# R_Phase_Sense_Signal_Isolation.net
KiCad netlist of a schematic drawn in Altium Designer
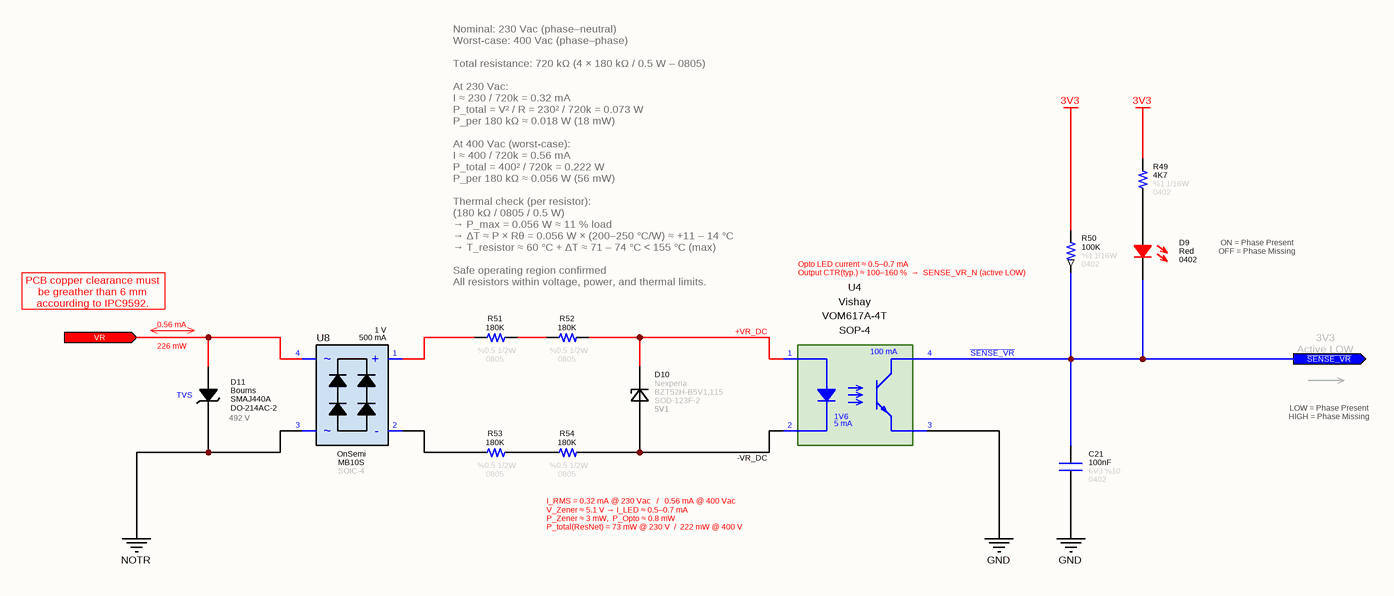
[diagram p0: R Phase Sense Signal Isolation.SchDoc]

(export (version "E")
  (design (tool "Eeschema 10.0.6"))
  (components
    (comp (ref "C21")
      (value "100nF")
      (footprint "CAPACITOR_0402")
      (description "Capacitor (MLCC) - 100nF / 6V3 / 0402")
      (fields
        (field (name "MANUFACTURER PART NUMBER") "04026D104KAT4A")
        (field (name "TOLERANCE") "%10")
        (field (name "VOLTAGE") "6V3")
        (field (name "CASE") "0402")
        (field (name "Comment") "Capacitor - 100nF [0402] (MLCC)")
      )
      (libsource (lib "Akkoyun") (part "Capacitor - 100nF [0402-6V3]"))
    )
    (comp (ref "D9")
      (value "SMD LED (Red)")
      (footprint "LED_0402")
      (description "Standard LEDs - SMD MINI-MOLD ULTRA COMPACT RED")
      (fields
        (field (name "MANUFACTURER PART NUMBER") "SML-P12VTT86R")
        (field (name "CASE") "0402")
        (field (name "COLOR") "Red")
      )
      (libsource (lib "Akkoyun") (part "Diode - LED (0402-Red)"))
    )
    (comp (ref "D10")
      (value "BZT52H-B5V1,115")
      (footprint "SOD-123F-2")
      (description "Zener Diodes BZT52H-B5V1/SOD123F/SOD2")
      (fields
        (field (name "ZENER VOLTAGE") "5V1")
        (field (name "MANUFACTURER NAME") "Nexperia")
        (field (name "MANUFACTURER PART NUMBER") "BZT52H-B5V1,115")
        (field (name "CASE") "SOD-123F-2")
      )
      (libsource (lib "Akkoyun") (part "Diode - BZT52H-B5V1,115"))
    )
    (comp (ref "D11")
      (value "SMAJ440A")
      (footprint "DO-220AA-2")
      (description "ESD Protection Diodes / TVS Diodes 440volts 1uA .6 Amps Uni-Dir")
      (fields
        (field (name "BREAKDOWN VOLTAGE") "492 V")
        (field (name "MANUFACTURER NAME") "Bourns")
        (field (name "MANUFACTURER PART NUMBER") "SMAJ440A")
        (field (name "CASE") "DO-214AC-2")
      )
      (libsource (lib "Akkoyun") (part "Diode - SMAJ440A (TVS)"))
    )
    (comp (ref "R49")
      (value "4K7")
      (footprint "RESISTOR_0402")
      (description "Thick Film Resistors - SMD 1/16 W 4.7 KOhm 1%")
      (fields
        (field (name "MANUFACTURER PART NUMBER") "CRCW04024K70FKED")
        (field (name "TOLERANCE") "%1")
        (field (name "CASE") "0402")
        (field (name "POWER") "1/16W")
        (field (name "Comment") "4K7 - 0402 - %1 - 1/16W")
      )
      (libsource (lib "Akkoyun") (part "Resistor - 4K7 [0402]"))
    )
    (comp (ref "R50")
      (value "100K")
      (footprint "RESISTOR_0402")
      (description "Thick Film Resistors - SMD 1/16 W 100 KOhm 1%")
      (fields
        (field (name "MANUFACTURER PART NUMBER") "CRCW0402100KFKED")
        (field (name "TOLERANCE") "%1")
        (field (name "CASE") "0402")
        (field (name "POWER") "1/16W")
        (field (name "Comment") "100K - 0402 - %1 - 1/16W")
      )
      (libsource (lib "Akkoyun") (part "Resistor - 100K [0402]"))
    )
    (comp (ref "R51")
      (value "180K")
      (footprint "RESISTOR_0805")
      (description "Thick Film Resistors - SMD 0805 180Kohms 0.5W 0.5% AEC-Q200")
      (fields
        (field (name "MANUFACTURER PART NUMBER") "ERJ-P06D1803V")
        (field (name "TOLERANCE") "%0.5")
        (field (name "CASE") "0805")
        (field (name "POWER") "1/2W")
        (field (name "Comment") "180K - 0805 - %0.5 - 1/2W")
      )
      (libsource (lib "Akkoyun") (part "Resistor - 180K [0805]"))
    )
    (comp (ref "R52")
      (value "180K")
      (footprint "RESISTOR_0805")
      (description "Thick Film Resistors - SMD 0805 180Kohms 0.5W 0.5% AEC-Q200")
      (fields
        (field (name "MANUFACTURER PART NUMBER") "ERJ-P06D1803V")
        (field (name "TOLERANCE") "%0.5")
        (field (name "CASE") "0805")
        (field (name "POWER") "1/2W")
        (field (name "Comment") "180K - 0805 - %0.5 - 1/2W")
      )
      (libsource (lib "Akkoyun") (part "Resistor - 180K [0805]"))
    )
    (comp (ref "R53")
      (value "180K")
      (footprint "RESISTOR_0805")
      (description "Thick Film Resistors - SMD 0805 180Kohms 0.5W 0.5% AEC-Q200")
      (fields
        (field (name "MANUFACTURER PART NUMBER") "ERJ-P06D1803V")
        (field (name "TOLERANCE") "%0.5")
        (field (name "CASE") "0805")
        (field (name "POWER") "1/2W")
        (field (name "Comment") "180K - 0805 - %0.5 - 1/2W")
      )
      (libsource (lib "Akkoyun") (part "Resistor - 180K [0805]"))
    )
    (comp (ref "R54")
      (value "180K")
      (footprint "RESISTOR_0805")
      (description "Thick Film Resistors - SMD 0805 180Kohms 0.5W 0.5% AEC-Q200")
      (fields
        (field (name "MANUFACTURER PART NUMBER") "ERJ-P06D1803V")
        (field (name "TOLERANCE") "%0.5")
        (field (name "CASE") "0805")
        (field (name "POWER") "1/2W")
        (field (name "Comment") "180K - 0805 - %0.5 - 1/2W")
      )
      (libsource (lib "Akkoyun") (part "Resistor - 180K [0805]"))
    )
    (comp (ref "U4")
      (value "VOM617A-4T")
      (footprint "SOP-4V2")
      (description "Transistor Output Optocouplers Phototransistor Out CTR 160-320% 5mA")
      (fields
        (field (name "MANUFACTURER PART NUMBER") "VOM617A-4T")
        (field (name "MANUFACTURER NAME") "Vishay")
        (field (name "CASE") "SOP-4")
        (field (name "IF - FORWARD CURRENT") "5 mA")
        (field (name "VF - FORWARD VOLTAGE") "1V6")
        (field (name "MAXIMUM COLLECTOR CURRENT") "100 mA")
      )
      (libsource (lib "Akkoyun") (part "IC - VOM617A"))
    )
    (comp (ref "U8")
      (value "LTV-846S")
      (footprint "SOIC-4")
      (description "Transistor Output Optocouplers Optocplr Phototrans 4-Channel")
      (fields
        (field (name "IF - FORWARD CURRENT") "500 mA")
        (field (name "VF - FORWARD VOLTAGE") "1 V")
        (field (name "MANUFACTURER NAME") "OnSemi")
        (field (name "MANUFACTURER PART NUMBER") "MB10S")
        (field (name "CASE") "SOIC-4")
      )
      (libsource (lib "Akkoyun") (part "IC - MB10S"))
    )
  )
  (nets
    (net (code "1") (name "/+VR_DC") (class "Default")
      (node (ref "D10") (pin "1") (pinfunction "Cathode_1") (pintype "passive"))
      (node (ref "R52") (pin "1") (pinfunction "1_1") (pintype "passive"))
      (node (ref "U4") (pin "1") (pinfunction "LED_Anode_1") (pintype "passive"))
    )
    (net (code "2") (name "/-VR_DC") (class "Default")
      (node (ref "D10") (pin "2") (pinfunction "Anode_2") (pintype "passive"))
      (node (ref "R54") (pin "1") (pinfunction "1_1") (pintype "passive"))
      (node (ref "U4") (pin "2") (pinfunction "LED_Cathode_2") (pintype "passive"))
    )
    (net (code "3") (name "/VR") (class "Default")
      (node (ref "D11") (pin "1") (pinfunction "Anode_1") (pintype "passive"))
      (node (ref "U8") (pin "4") (pinfunction "~_4") (pintype "passive"))
    )
    (net (code "4") (name "/~{SENSE_VR}") (class "Default")
      (node (ref "C21") (pin "2") (pinfunction "2_2") (pintype "passive"))
      (node (ref "D9") (pin "1") (pinfunction "1_1") (pintype "passive"))
      (node (ref "R50") (pin "1") (pinfunction "1_1") (pintype "output"))
      (node (ref "U4") (pin "4") (pinfunction "Collector_4") (pintype "passive"))
    )
    (net (code "5") (name "3V3") (class "Default")
      (node (ref "R49") (pin "2") (pinfunction "2_2") (pintype "passive"))
      (node (ref "R50") (pin "2") (pinfunction "2_2") (pintype "passive"))
    )
    (net (code "6") (name "GND") (class "Default")
      (node (ref "C21") (pin "1") (pinfunction "1_1") (pintype "passive"))
      (node (ref "U4") (pin "3") (pinfunction "Emiter_3") (pintype "passive"))
    )
    (net (code "7") (name "NOTR") (class "Default")
      (node (ref "D11") (pin "2") (pinfunction "Cathode_2") (pintype "passive"))
      (node (ref "U8") (pin "3") (pinfunction "~_3") (pintype "passive"))
    )
    (net (code "8") (name "Net-(D9-Pad2)") (class "Default")
      (node (ref "D9") (pin "2") (pinfunction "2_2") (pintype "passive"))
      (node (ref "R49") (pin "1") (pinfunction "1_1") (pintype "passive"))
    )
    (net (code "9") (name "Net-(R51-Pad1)") (class "Default")
      (node (ref "R51") (pin "1") (pinfunction "1_1") (pintype "passive"))
      (node (ref "R52") (pin "2") (pinfunction "2_2") (pintype "passive"))
    )
    (net (code "10") (name "Net-(R53-Pad1)") (class "Default")
      (node (ref "R53") (pin "1") (pinfunction "1_1") (pintype "passive"))
      (node (ref "R54") (pin "2") (pinfunction "2_2") (pintype "passive"))
    )
    (net (code "11") (name "Net-(U8-+)") (class "Default")
      (node (ref "R51") (pin "2") (pinfunction "2_2") (pintype "passive"))
      (node (ref "U8") (pin "1") (pinfunction "+_1") (pintype "passive"))
    )
    (net (code "12") (name "Net-(U8--)") (class "Default")
      (node (ref "R53") (pin "2") (pinfunction "2_2") (pintype "passive"))
      (node (ref "U8") (pin "2") (pinfunction "-_2") (pintype "passive"))
    )
  )
)
